# controller.net
KiCad netlist of a schematic drawn in EAGLE
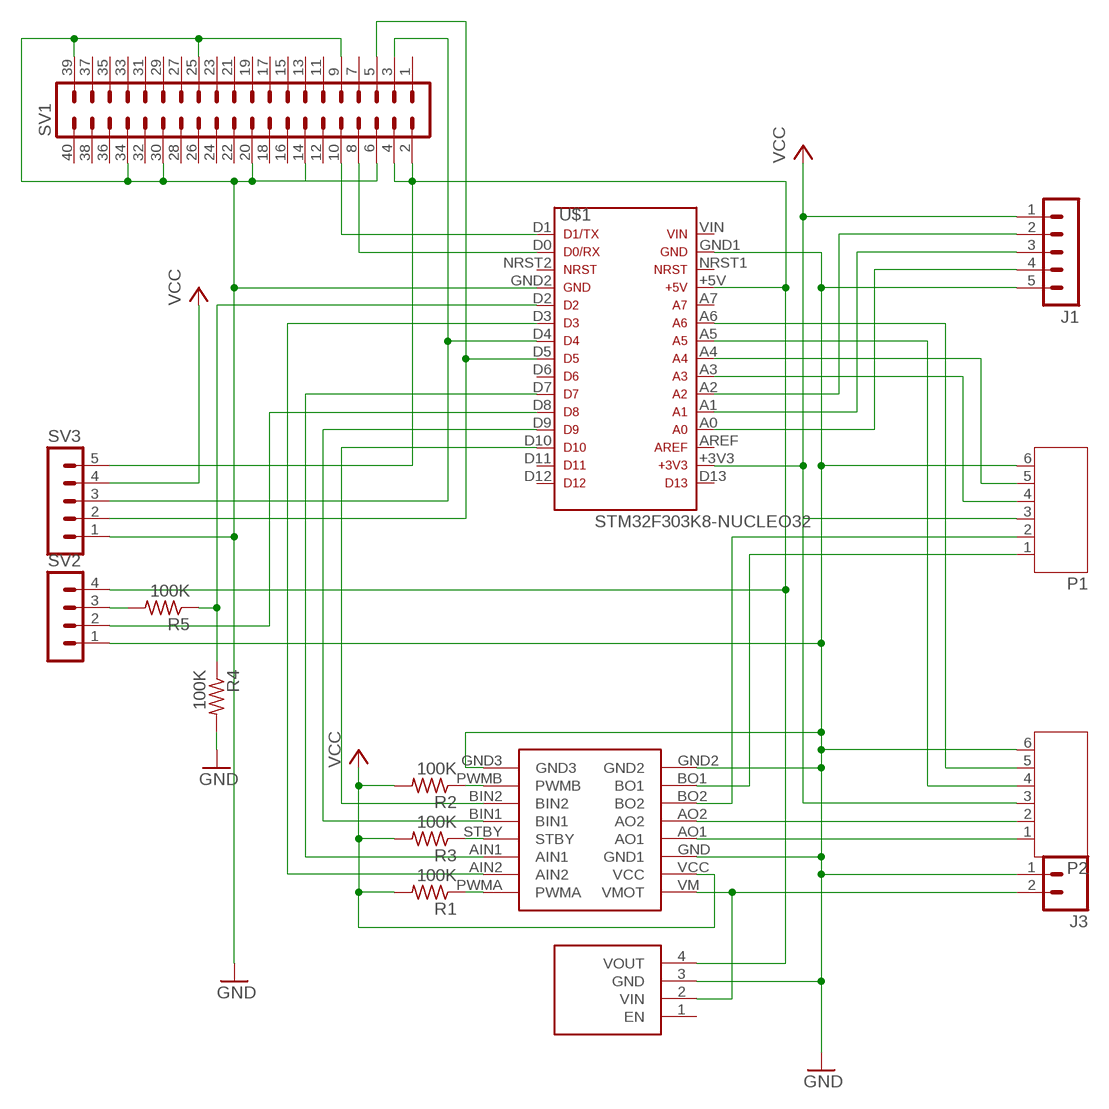
[diagram p0: schematic, sheet 1]

(export (version "E")
  (design (tool "Eeschema 10.0.6"))
  (components
    (comp (ref "J1")
      (value "MA05-1")
      (footprint "eagle-import:MA05-1")
      (libsource (lib "eagle-import") (part "MA05-1"))
    )
    (comp (ref "J3")
      (value "M02JST-PTH-VERT")
      (footprint "eagle-import:JST-2-PTH-VERT")
      (libsource (lib "eagle-import") (part "M02JST-PTH-VERT"))
    )
    (comp (ref "P1")
      (value "JST-PH6")
      (footprint "eagle-import:JST-PH6")
      (libsource (lib "eagle-import") (part "JST-PH6"))
    )
    (comp (ref "P2")
      (value "JST-PH6")
      (footprint "eagle-import:JST-PH6")
      (libsource (lib "eagle-import") (part "JST-PH6"))
    )
    (comp (ref "R1")
      (value "100K")
      (footprint "eagle-import:M0805")
      (libsource (lib "eagle-import") (part "R-US_M0805"))
    )
    (comp (ref "R2")
      (value "100K")
      (footprint "eagle-import:M0805")
      (libsource (lib "eagle-import") (part "R-US_M0805"))
    )
    (comp (ref "R3")
      (value "100K")
      (footprint "eagle-import:M0805")
      (libsource (lib "eagle-import") (part "R-US_M0805"))
    )
    (comp (ref "R4")
      (value "100K")
      (footprint "eagle-import:M0805")
      (libsource (lib "eagle-import") (part "R-US_M0805"))
    )
    (comp (ref "R5")
      (value "100K")
      (footprint "eagle-import:M0805")
      (libsource (lib "eagle-import") (part "R-US_M0805"))
    )
    (comp (ref "SV1")
      (value "MA20-2")
      (footprint "eagle-import:MA20-2")
      (libsource (lib "eagle-import") (part "MA20-2"))
    )
    (comp (ref "SV2")
      (value "MA04-1")
      (footprint "eagle-import:MA04-1")
      (libsource (lib "eagle-import") (part "MA04-1"))
    )
    (comp (ref "SV3")
      (value "MA05-1")
      (footprint "eagle-import:MA05-1")
      (libsource (lib "eagle-import") (part "MA05-1"))
    )
    (comp (ref "U$1")
      (value "STM32F303K8-NUCLEO32")
      (footprint "eagle-import:NUCLEO32")
      (libsource (lib "eagle-import") (part "STM32F303K8-NUCLEO32"))
    )
    (comp (ref "U$2")
      (value "TB6612FNG-CARRIER/SPARKFUN")
      (footprint "eagle-import:TB6612FNG-BRKOUT_SPARKFUN")
      (libsource (lib "eagle-import") (part "TB6612FNG-CARRIER/SPARKFUN"))
    )
    (comp (ref "U$3")
      (value "S7V8A")
      (footprint "eagle-import:S7V8")
      (libsource (lib "eagle-import") (part "S7V8A"))
    )
  )
  (nets
    (net (code "1") (name "GND") (class "Default")
      (node (ref "J1") (pin "5") (pinfunction "5_5") (pintype "passive"))
      (node (ref "J3") (pin "1") (pinfunction "1_1") (pintype "passive"))
      (node (ref "P1") (pin "6") (pinfunction "6_6") (pintype "passive"))
      (node (ref "P2") (pin "6") (pinfunction "6_6") (pintype "passive"))
      (node (ref "R4") (pin "2") (pinfunction "2_2") (pintype "passive"))
      (node (ref "SV1") (pin "14") (pinfunction "14_14") (pintype "passive"))
      (node (ref "SV1") (pin "20") (pinfunction "20_20") (pintype "passive"))
      (node (ref "SV1") (pin "25") (pinfunction "25_25") (pintype "passive"))
      (node (ref "SV1") (pin "30") (pinfunction "30_30") (pintype "passive"))
      (node (ref "SV1") (pin "34") (pinfunction "34_34") (pintype "passive"))
      (node (ref "SV1") (pin "39") (pinfunction "39_39") (pintype "passive"))
      (node (ref "SV1") (pin "6") (pinfunction "6_6") (pintype "passive"))
      (node (ref "SV1") (pin "9") (pinfunction "9_9") (pintype "passive"))
      (node (ref "SV2") (pin "1") (pinfunction "1_1") (pintype "passive"))
      (node (ref "SV3") (pin "1") (pinfunction "1_1") (pintype "passive"))
      (node (ref "U$1") (pin "GND1") (pinfunction "GND1_GND1") (pintype "passive"))
      (node (ref "U$1") (pin "GND2") (pinfunction "GND2_GND2") (pintype "passive"))
      (node (ref "U$2") (pin "GND") (pinfunction "GND1_GND") (pintype "bidirectional"))
      (node (ref "U$2") (pin "GND2") (pinfunction "GND2_GND2") (pintype "bidirectional"))
      (node (ref "U$2") (pin "GND3") (pinfunction "GND3_GND3") (pintype "bidirectional"))
      (node (ref "U$3") (pin "3") (pinfunction "GND_3") (pintype "bidirectional"))
    )
    (net (code "2") (name "Net-(J1-Pad2)") (class "Default")
      (node (ref "J1") (pin "2") (pinfunction "2_2") (pintype "passive"))
      (node (ref "U$1") (pin "A2") (pinfunction "A2_A2") (pintype "passive"))
    )
    (net (code "3") (name "Net-(J1-Pad3)") (class "Default")
      (node (ref "J1") (pin "3") (pinfunction "3_3") (pintype "passive"))
      (node (ref "U$1") (pin "A1") (pinfunction "A1_A1") (pintype "passive"))
    )
    (net (code "4") (name "Net-(J1-Pad4)") (class "Default")
      (node (ref "J1") (pin "4") (pinfunction "4_4") (pintype "passive"))
      (node (ref "U$1") (pin "A0") (pinfunction "A0_A0") (pintype "passive"))
    )
    (net (code "5") (name "Net-(P1-Pad1)") (class "Default")
      (node (ref "P1") (pin "1") (pinfunction "1_1") (pintype "passive"))
      (node (ref "U$2") (pin "BO1") (pinfunction "BO1_BO1") (pintype "bidirectional"))
    )
    (net (code "6") (name "Net-(P1-Pad2)") (class "Default")
      (node (ref "P1") (pin "2") (pinfunction "2_2") (pintype "passive"))
      (node (ref "U$2") (pin "BO2") (pinfunction "BO2_BO2") (pintype "bidirectional"))
    )
    (net (code "7") (name "Net-(P1-Pad4)") (class "Default")
      (node (ref "P1") (pin "4") (pinfunction "4_4") (pintype "passive"))
      (node (ref "U$1") (pin "A3") (pinfunction "A3_A3") (pintype "passive"))
    )
    (net (code "8") (name "Net-(P1-Pad5)") (class "Default")
      (node (ref "P1") (pin "5") (pinfunction "5_5") (pintype "passive"))
      (node (ref "U$1") (pin "A4") (pinfunction "A4_A4") (pintype "passive"))
    )
    (net (code "9") (name "Net-(P2-Pad1)") (class "Default")
      (node (ref "P2") (pin "1") (pinfunction "1_1") (pintype "passive"))
      (node (ref "U$2") (pin "AO1") (pinfunction "AO1_AO1") (pintype "bidirectional"))
    )
    (net (code "10") (name "Net-(P2-Pad2)") (class "Default")
      (node (ref "P2") (pin "2") (pinfunction "2_2") (pintype "passive"))
      (node (ref "U$2") (pin "AO2") (pinfunction "AO2_AO2") (pintype "bidirectional"))
    )
    (net (code "11") (name "Net-(P2-Pad4)") (class "Default")
      (node (ref "P2") (pin "4") (pinfunction "4_4") (pintype "passive"))
      (node (ref "U$1") (pin "A5") (pinfunction "A5_A5") (pintype "passive"))
    )
    (net (code "12") (name "Net-(P2-Pad5)") (class "Default")
      (node (ref "P2") (pin "5") (pinfunction "5_5") (pintype "passive"))
      (node (ref "U$1") (pin "A6") (pinfunction "A6_A6") (pintype "passive"))
    )
    (net (code "13") (name "Net-(R1-Pad1)") (class "Default")
      (node (ref "R1") (pin "1") (pinfunction "1_1") (pintype "passive"))
      (node (ref "U$2") (pin "PWMA") (pinfunction "PWMA_PWMA") (pintype "bidirectional"))
    )
    (net (code "14") (name "Net-(R2-Pad1)") (class "Default")
      (node (ref "R2") (pin "1") (pinfunction "1_1") (pintype "passive"))
      (node (ref "U$2") (pin "PWMB") (pinfunction "PWMB_PWMB") (pintype "bidirectional"))
    )
    (net (code "15") (name "Net-(R3-Pad1)") (class "Default")
      (node (ref "R3") (pin "1") (pinfunction "1_1") (pintype "passive"))
      (node (ref "U$2") (pin "STBY") (pinfunction "STBY_STBY") (pintype "bidirectional"))
    )
    (net (code "16") (name "Net-(R4-Pad1)") (class "Default")
      (node (ref "R4") (pin "1") (pinfunction "1_1") (pintype "passive"))
      (node (ref "R5") (pin "1") (pinfunction "1_1") (pintype "passive"))
      (node (ref "U$1") (pin "D2") (pinfunction "D2_D2") (pintype "passive"))
    )
    (net (code "17") (name "Net-(R5-Pad2)") (class "Default")
      (node (ref "R5") (pin "2") (pinfunction "2_2") (pintype "passive"))
      (node (ref "SV2") (pin "3") (pinfunction "3_3") (pintype "passive"))
    )
    (net (code "18") (name "Net-(SV1-Pad3)") (class "Default")
      (node (ref "SV1") (pin "3") (pinfunction "3_3") (pintype "passive"))
      (node (ref "SV3") (pin "3") (pinfunction "3_3") (pintype "passive"))
      (node (ref "U$1") (pin "D4") (pinfunction "D4_D4") (pintype "passive"))
    )
    (net (code "19") (name "Net-(SV1-Pad5)") (class "Default")
      (node (ref "SV1") (pin "5") (pinfunction "5_5") (pintype "passive"))
      (node (ref "SV3") (pin "2") (pinfunction "2_2") (pintype "passive"))
      (node (ref "U$1") (pin "D5") (pinfunction "D5_D5") (pintype "passive"))
    )
    (net (code "20") (name "Net-(SV1-Pad8)") (class "Default")
      (node (ref "SV1") (pin "8") (pinfunction "8_8") (pintype "passive"))
      (node (ref "U$1") (pin "D0") (pinfunction "D0_D0") (pintype "passive"))
    )
    (net (code "21") (name "Net-(SV1-Pad10)") (class "Default")
      (node (ref "SV1") (pin "10") (pinfunction "10_10") (pintype "passive"))
      (node (ref "U$1") (pin "D1") (pinfunction "D1_D1") (pintype "passive"))
    )
    (net (code "22") (name "Net-(SV2-Pad2)") (class "Default")
      (node (ref "SV2") (pin "2") (pinfunction "2_2") (pintype "passive"))
      (node (ref "U$1") (pin "D8") (pinfunction "D8_D8") (pintype "passive"))
    )
    (net (code "23") (name "Net-(U$1-PadD3)") (class "Default")
      (node (ref "U$1") (pin "D3") (pinfunction "D3_D3") (pintype "passive"))
      (node (ref "U$2") (pin "AIN2") (pinfunction "AIN2_AIN2") (pintype "bidirectional"))
    )
    (net (code "24") (name "Net-(U$1-PadD7)") (class "Default")
      (node (ref "U$1") (pin "D7") (pinfunction "D7_D7") (pintype "passive"))
      (node (ref "U$2") (pin "AIN1") (pinfunction "AIN1_AIN1") (pintype "bidirectional"))
    )
    (net (code "25") (name "Net-(U$1-PadD9)") (class "Default")
      (node (ref "U$1") (pin "D9") (pinfunction "D9_D9") (pintype "passive"))
      (node (ref "U$2") (pin "BIN1") (pinfunction "BIN1_BIN1") (pintype "bidirectional"))
    )
    (net (code "26") (name "Net-(U$1-PadD10)") (class "Default")
      (node (ref "U$1") (pin "D10") (pinfunction "D10_D10") (pintype "passive"))
      (node (ref "U$2") (pin "BIN2") (pinfunction "BIN2_BIN2") (pintype "bidirectional"))
    )
    (net (code "27") (name "Net-(U$2-VMOT)") (class "Default")
      (node (ref "J3") (pin "2") (pinfunction "2_2") (pintype "passive"))
      (node (ref "U$2") (pin "VM") (pinfunction "VMOT_VM") (pintype "bidirectional"))
      (node (ref "U$3") (pin "2") (pinfunction "VIN_2") (pintype "bidirectional"))
    )
    (net (code "28") (name "Net-(U$3-VOUT)") (class "Default")
      (node (ref "SV1") (pin "2") (pinfunction "2_2") (pintype "passive"))
      (node (ref "SV1") (pin "4") (pinfunction "4_4") (pintype "passive"))
      (node (ref "SV2") (pin "4") (pinfunction "4_4") (pintype "passive"))
      (node (ref "SV3") (pin "5") (pinfunction "5_5") (pintype "passive"))
      (node (ref "U$1") (pin "+5V") (pinfunction "+5V_+5V") (pintype "passive"))
      (node (ref "U$3") (pin "4") (pinfunction "VOUT_4") (pintype "bidirectional"))
    )
    (net (code "29") (name "VCC") (class "Default")
      (node (ref "J1") (pin "1") (pinfunction "1_1") (pintype "passive"))
      (node (ref "P1") (pin "3") (pinfunction "3_3") (pintype "passive"))
      (node (ref "P2") (pin "3") (pinfunction "3_3") (pintype "passive"))
      (node (ref "R1") (pin "2") (pinfunction "2_2") (pintype "passive"))
      (node (ref "R2") (pin "2") (pinfunction "2_2") (pintype "passive"))
      (node (ref "R3") (pin "2") (pinfunction "2_2") (pintype "passive"))
      (node (ref "SV3") (pin "4") (pinfunction "4_4") (pintype "passive"))
      (node (ref "U$1") (pin "+3V3") (pinfunction "+3V3_+3V3") (pintype "passive"))
      (node (ref "U$2") (pin "VCC") (pinfunction "VCC_VCC") (pintype "bidirectional"))
    )
    (net (code "30") (name "unconnected-(SV1-Pad1)") (class "Default")
      (node (ref "SV1") (pin "1") (pinfunction "1_1") (pintype "passive"))
    )
    (net (code "31") (name "unconnected-(SV1-Pad7)") (class "Default")
      (node (ref "SV1") (pin "7") (pinfunction "7_7") (pintype "passive"))
    )
    (net (code "32") (name "unconnected-(SV1-Pad11)") (class "Default")
      (node (ref "SV1") (pin "11") (pinfunction "11_11") (pintype "passive"))
    )
    (net (code "33") (name "unconnected-(SV1-Pad12)") (class "Default")
      (node (ref "SV1") (pin "12") (pinfunction "12_12") (pintype "passive"))
    )
    (net (code "34") (name "unconnected-(SV1-Pad13)") (class "Default")
      (node (ref "SV1") (pin "13") (pinfunction "13_13") (pintype "passive"))
    )
    (net (code "35") (name "unconnected-(SV1-Pad15)") (class "Default")
      (node (ref "SV1") (pin "15") (pinfunction "15_15") (pintype "passive"))
    )
    (net (code "36") (name "unconnected-(SV1-Pad16)") (class "Default")
      (node (ref "SV1") (pin "16") (pinfunction "16_16") (pintype "passive"))
    )
    (net (code "37") (name "unconnected-(SV1-Pad17)") (class "Default")
      (node (ref "SV1") (pin "17") (pinfunction "17_17") (pintype "passive"))
    )
    (net (code "38") (name "unconnected-(SV1-Pad18)") (class "Default")
      (node (ref "SV1") (pin "18") (pinfunction "18_18") (pintype "passive"))
    )
    (net (code "39") (name "unconnected-(SV1-Pad19)") (class "Default")
      (node (ref "SV1") (pin "19") (pinfunction "19_19") (pintype "passive"))
    )
    (net (code "40") (name "unconnected-(SV1-Pad21)") (class "Default")
      (node (ref "SV1") (pin "21") (pinfunction "21_21") (pintype "passive"))
    )
    (net (code "41") (name "unconnected-(SV1-Pad22)") (class "Default")
      (node (ref "SV1") (pin "22") (pinfunction "22_22") (pintype "passive"))
    )
    (net (code "42") (name "unconnected-(SV1-Pad23)") (class "Default")
      (node (ref "SV1") (pin "23") (pinfunction "23_23") (pintype "passive"))
    )
    (net (code "43") (name "unconnected-(SV1-Pad24)") (class "Default")
      (node (ref "SV1") (pin "24") (pinfunction "24_24") (pintype "passive"))
    )
    (net (code "44") (name "unconnected-(SV1-Pad26)") (class "Default")
      (node (ref "SV1") (pin "26") (pinfunction "26_26") (pintype "passive"))
    )
    (net (code "45") (name "unconnected-(SV1-Pad27)") (class "Default")
      (node (ref "SV1") (pin "27") (pinfunction "27_27") (pintype "passive"))
    )
    (net (code "46") (name "unconnected-(SV1-Pad28)") (class "Default")
      (node (ref "SV1") (pin "28") (pinfunction "28_28") (pintype "passive"))
    )
    (net (code "47") (name "unconnected-(SV1-Pad29)") (class "Default")
      (node (ref "SV1") (pin "29") (pinfunction "29_29") (pintype "passive"))
    )
    (net (code "48") (name "unconnected-(SV1-Pad31)") (class "Default")
      (node (ref "SV1") (pin "31") (pinfunction "31_31") (pintype "passive"))
    )
    (net (code "49") (name "unconnected-(SV1-Pad32)") (class "Default")
      (node (ref "SV1") (pin "32") (pinfunction "32_32") (pintype "passive"))
    )
    (net (code "50") (name "unconnected-(SV1-Pad33)") (class "Default")
      (node (ref "SV1") (pin "33") (pinfunction "33_33") (pintype "passive"))
    )
    (net (code "51") (name "unconnected-(SV1-Pad35)") (class "Default")
      (node (ref "SV1") (pin "35") (pinfunction "35_35") (pintype "passive"))
    )
    (net (code "52") (name "unconnected-(SV1-Pad36)") (class "Default")
      (node (ref "SV1") (pin "36") (pinfunction "36_36") (pintype "passive"))
    )
    (net (code "53") (name "unconnected-(SV1-Pad37)") (class "Default")
      (node (ref "SV1") (pin "37") (pinfunction "37_37") (pintype "passive"))
    )
    (net (code "54") (name "unconnected-(SV1-Pad38)") (class "Default")
      (node (ref "SV1") (pin "38") (pinfunction "38_38") (pintype "passive"))
    )
    (net (code "55") (name "unconnected-(SV1-Pad40)") (class "Default")
      (node (ref "SV1") (pin "40") (pinfunction "40_40") (pintype "passive"))
    )
    (net (code "56") (name "unconnected-(U$1-PadA7)") (class "Default")
      (node (ref "U$1") (pin "A7") (pinfunction "A7_A7") (pintype "passive"))
    )
    (net (code "57") (name "unconnected-(U$1-PadAREF)") (class "Default")
      (node (ref "U$1") (pin "AREF") (pinfunction "AREF_AREF") (pintype "passive"))
    )
    (net (code "58") (name "unconnected-(U$1-PadD6)") (class "Default")
      (node (ref "U$1") (pin "D6") (pinfunction "D6_D6") (pintype "passive"))
    )
    (net (code "59") (name "unconnected-(U$1-PadD11)") (class "Default")
      (node (ref "U$1") (pin "D11") (pinfunction "D11_D11") (pintype "passive"))
    )
    (net (code "60") (name "unconnected-(U$1-PadD12)") (class "Default")
      (node (ref "U$1") (pin "D12") (pinfunction "D12_D12") (pintype "passive"))
    )
    (net (code "61") (name "unconnected-(U$1-PadD13)") (class "Default")
      (node (ref "U$1") (pin "D13") (pinfunction "D13_D13") (pintype "passive"))
    )
    (net (code "62") (name "unconnected-(U$1-PadNRST1)") (class "Default")
      (node (ref "U$1") (pin "NRST1") (pinfunction "NRST1_NRST1") (pintype "passive"))
    )
    (net (code "63") (name "unconnected-(U$1-PadNRST2)") (class "Default")
      (node (ref "U$1") (pin "NRST2") (pinfunction "NRST2_NRST2") (pintype "passive"))
    )
    (net (code "64") (name "unconnected-(U$1-PadVIN)") (class "Default")
      (node (ref "U$1") (pin "VIN") (pinfunction "VIN_VIN") (pintype "passive"))
    )
    (net (code "65") (name "unconnected-(U$3-EN-Pad1)") (class "Default")
      (node (ref "U$3") (pin "1") (pinfunction "EN_1") (pintype "bidirectional"))
    )
  )
)
